# SCH_23x10_IO_EXTENDER_2023-06-17.net
KiCad netlist of a schematic drawn in EasyEDA
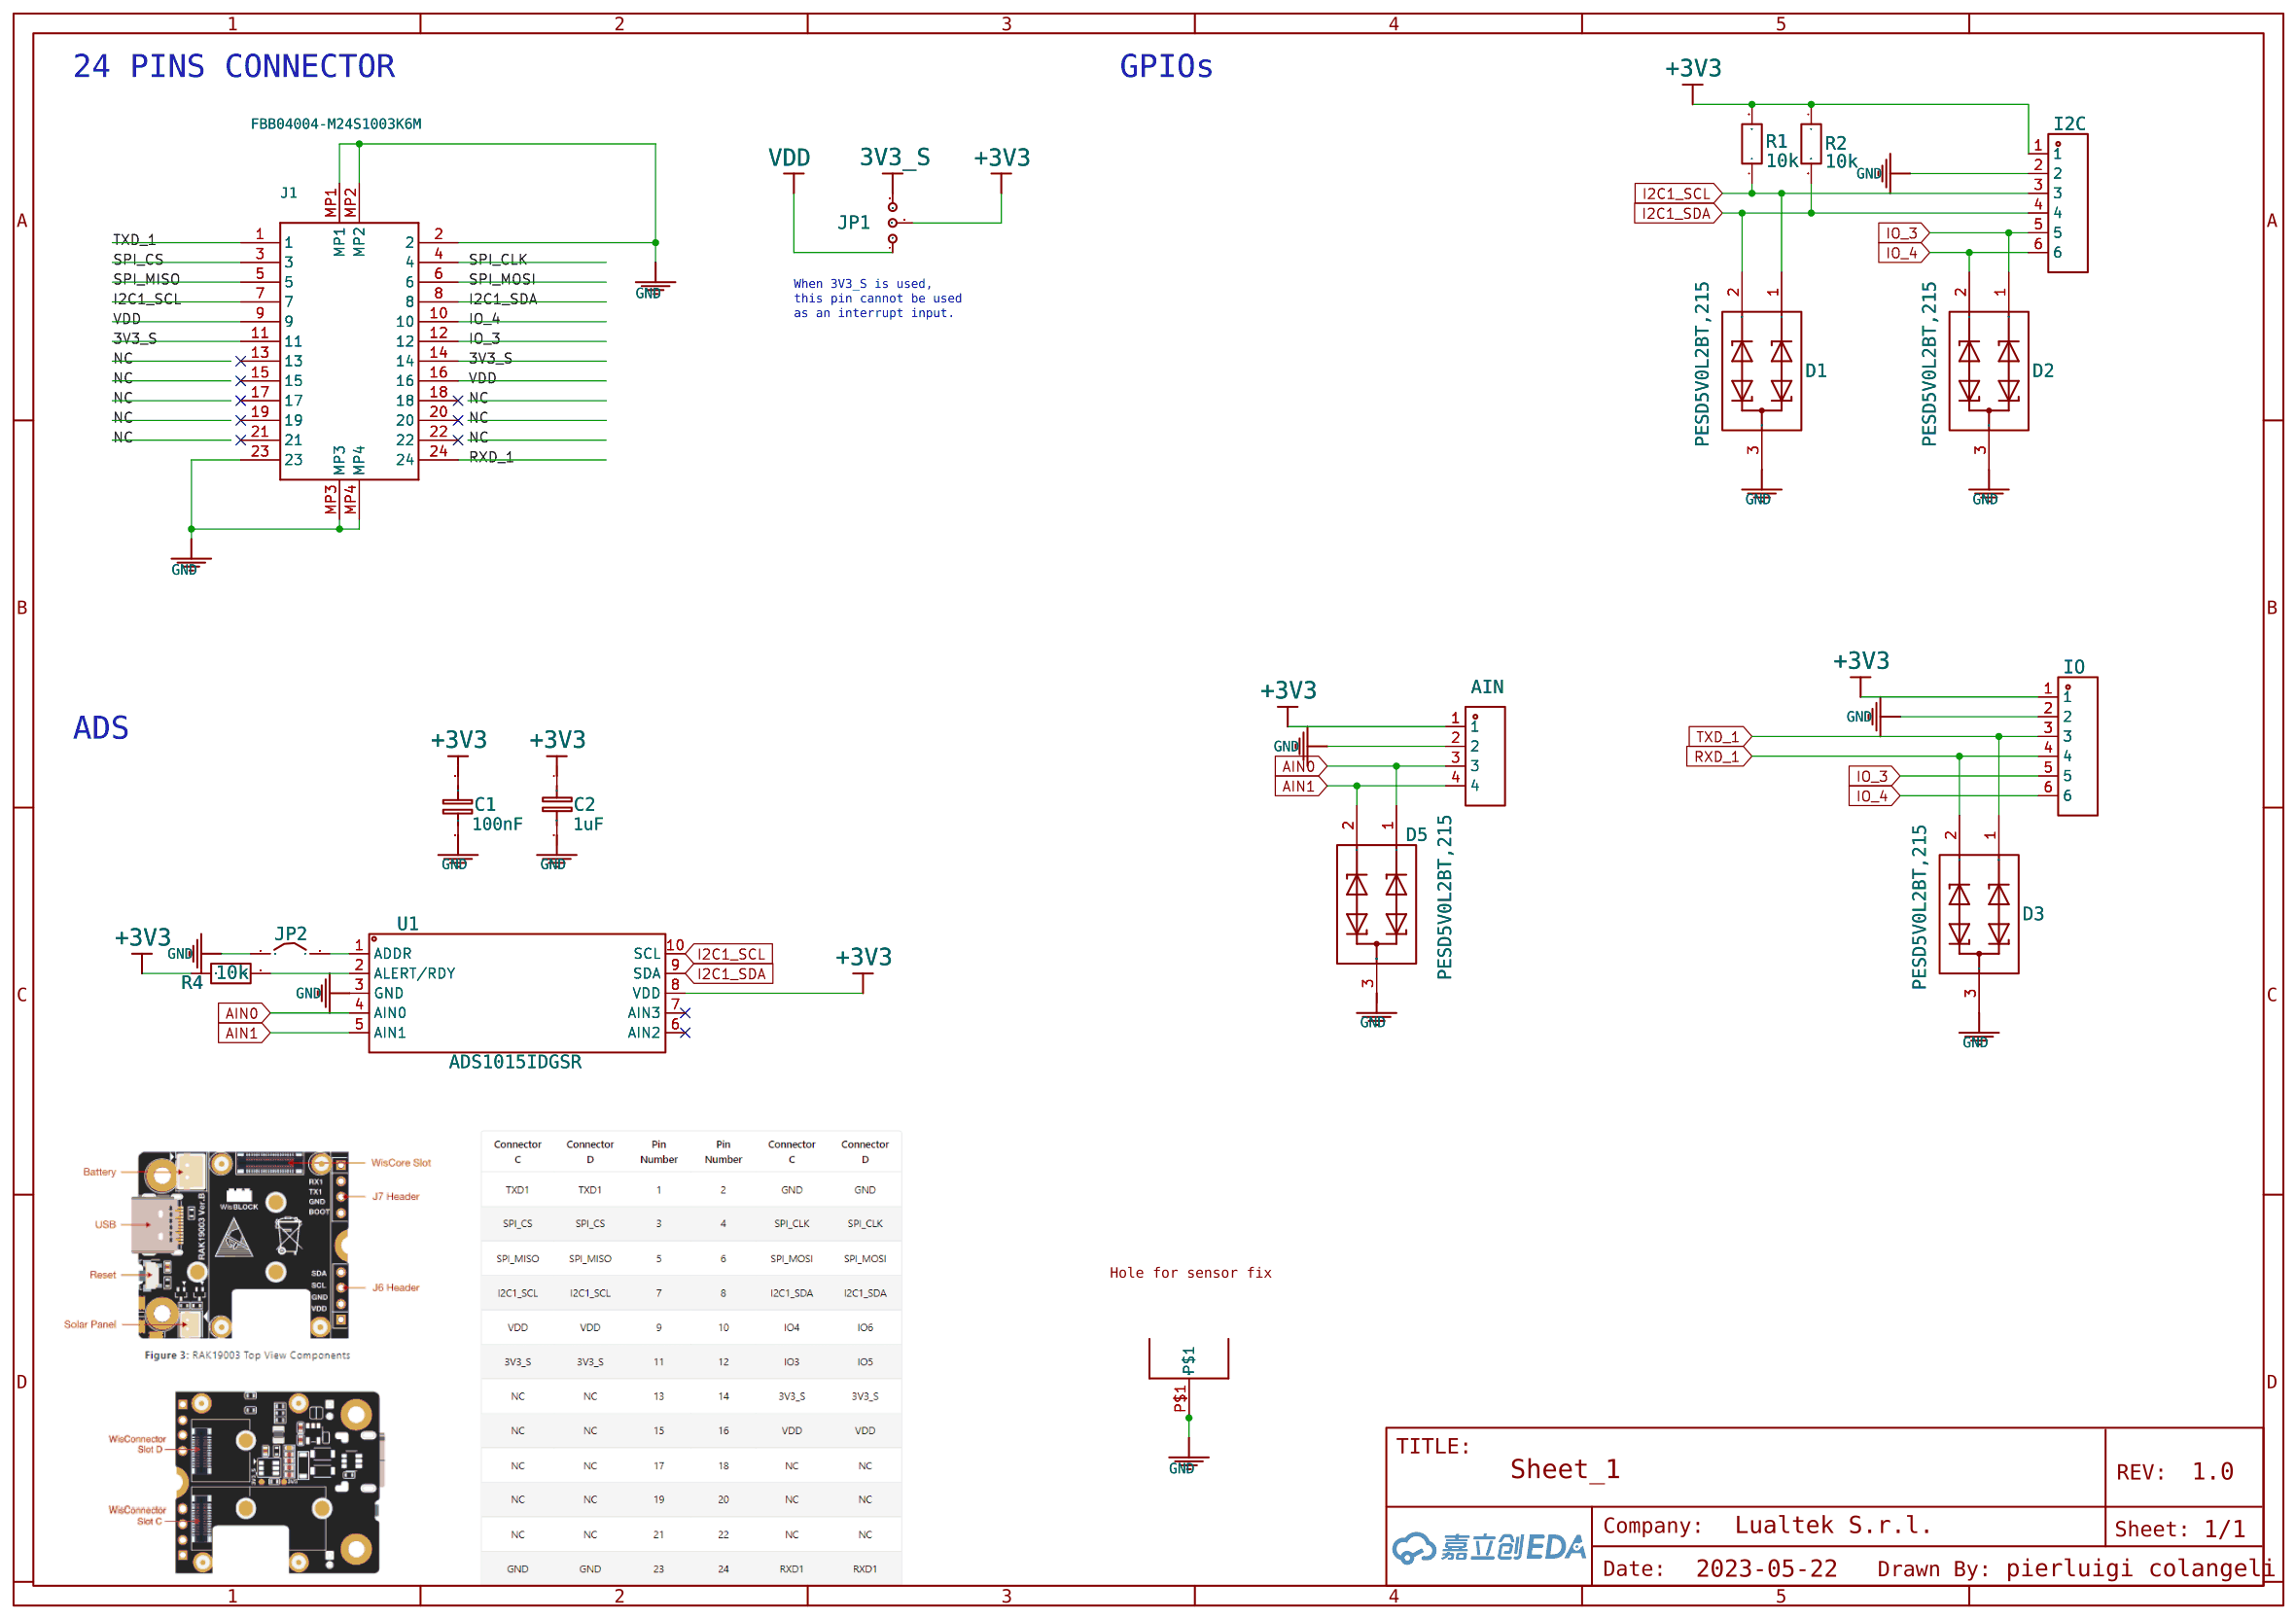
[diagram p0: schematic sheet]

(export (version "E")
  (design (tool "Eeschema 10.0.6"))
  (components
    (comp (ref "AIN")
      (value "J3")
      (fields
        (field (name "BOM_Manufacturer Part") "SM04B-SRSS-TB")
        (field (name "BOM_Supplier Part") "SM02B-SRSS-TB")
      )
      (libsource (lib "") (part "JST SH 4 pin side entry"))
    )
    (comp (ref "C1")
      (value "100nF")
      (fields
        (field (name "BOM_Manufacturer Part") "CC0603KRX7R9BB104")
        (field (name "BOM_Supplier Part") "C14663")
      )
      (libsource (lib "") (part "C_0603_EU"))
    )
    (comp (ref "C2")
      (value "1uF")
      (fields
        (field (name "BOM_Manufacturer Part") "CL10A105KB8NNNC")
        (field (name "BOM_Supplier Part") "C15849")
      )
      (libsource (lib "") (part "C_0603_EU_1"))
    )
    (comp (ref "D1")
      (value "PESD5V0L2BT,215")
      (fields (field (name "BOM_Supplier Part") "C12324"))
      (libsource (lib "") (part "PESD5V0L2BT,215"))
    )
    (comp (ref "D2")
      (value "PESD5V0L2BT,215")
      (fields (field (name "BOM_Supplier Part") "C12324"))
      (libsource (lib "") (part "PESD5V0L2BT,215"))
    )
    (comp (ref "D3")
      (value "PESD5V0L2BT,215")
      (fields (field (name "BOM_Supplier Part") "C12324"))
      (libsource (lib "") (part "PESD5V0L2BT,215"))
    )
    (comp (ref "D5")
      (value "PESD5V0L2BT,215")
      (fields (field (name "BOM_Supplier Part") "C12324"))
      (libsource (lib "") (part "PESD5V0L2BT,215"))
    )
    (comp (ref "I2C")
      (value "J1")
      (fields (field (name "BOM_Manufacturer Part") "SM06B-SRSS-TB"))
      (libsource (lib "") (part "JST SH 6 pin side entry"))
    )
    (comp (ref "IO")
      (value "J1")
      (fields (field (name "BOM_Manufacturer Part") "SM06B-SRSS-TB"))
      (libsource (lib "") (part "JST SH 6 pin side entry_1"))
    )
    (comp (ref "J1") (value "FBB04004-M24S1003K6M") (libsource (lib "") (part "Unknown_175_-720")))
    (comp (ref "JP1") (value "JUMPER_3WAY_NO_SMALL") (libsource (lib "") (part "JUMPER_3WAY_NO_SMALL")))
    (comp (ref "JP2") (value "Jumper") (libsource (lib "") (part "Jumper Solder Bridge SMD")))
    (comp (ref "R1")
      (value "10k")
      (fields
        (field (name "BOM_Manufacturer Part") "0603WAF1002T5E")
        (field (name "BOM_Supplier Part") "C25804")
      )
      (libsource (lib "") (part "R_0603_EU"))
    )
    (comp (ref "R2")
      (value "10k")
      (fields
        (field (name "BOM_Manufacturer Part") "0603WAF1002T5E")
        (field (name "BOM_Supplier Part") "C25804")
      )
      (libsource (lib "") (part "R_0603_EU_1"))
    )
    (comp (ref "R4")
      (value "10k")
      (fields
        (field (name "BOM_Manufacturer Part") "0603WAF1002T5E")
        (field (name "BOM_Supplier Part") "C25804")
      )
      (libsource (lib "") (part "R_0805_EU"))
    )
    (comp (ref "U$1") (value "RAK_SENSOR_FIX") (libsource (lib "") (part "Unknown_595_-135")))
    (comp (ref "U1")
      (value "ADS1015IDGSR")
      (fields (field (name "BOM_Supplier Part") "C193969"))
      (libsource (lib "") (part "ADS1015IDGSR"))
    )
  )
  (nets
    (net (code "1") (name "+3V3") (class "Default")
      (node (ref "AIN") (pin "1") (pinfunction "1_1") (pintype "unspecified"))
      (node (ref "C1") (pin "2") (pinfunction "2_2") (pintype "unspecified"))
      (node (ref "C2") (pin "1") (pinfunction "1_1") (pintype "unspecified"))
      (node (ref "I2C") (pin "1") (pinfunction "1_1") (pintype "unspecified"))
      (node (ref "IO") (pin "1") (pinfunction "1_1") (pintype "unspecified"))
      (node (ref "JP1") (pin "2") (pinfunction "2_2") (pintype "unspecified"))
      (node (ref "R1") (pin "2") (pinfunction "2_2") (pintype "unspecified"))
      (node (ref "R2") (pin "1") (pinfunction "1_1") (pintype "unspecified"))
      (node (ref "R4") (pin "1") (pinfunction "1_1") (pintype "unspecified"))
      (node (ref "U1") (pin "8") (pinfunction "VDD_8") (pintype "unspecified"))
    )
    (net (code "3") (name "/SPI_CLK") (class "Default")
      (node (ref "J1") (pin "4") (pinfunction "4_4") (pintype "bidirectional"))
    )
    (net (code "4") (name "/SPI_CS") (class "Default")
      (node (ref "J1") (pin "3") (pinfunction "3_3") (pintype "bidirectional"))
    )
    (net (code "5") (name "/SPI_MISO") (class "Default")
      (node (ref "J1") (pin "5") (pinfunction "5_5") (pintype "bidirectional"))
    )
    (net (code "6") (name "/SPI_MOSI") (class "Default")
      (node (ref "J1") (pin "6") (pinfunction "6_6") (pintype "bidirectional"))
    )
    (net (code "7") (name "3V3_S") (class "Default")
      (node (ref "J1") (pin "11") (pinfunction "11_11") (pintype "bidirectional"))
      (node (ref "J1") (pin "14") (pinfunction "14_14") (pintype "bidirectional"))
      (node (ref "JP1") (pin "3") (pinfunction "3_3") (pintype "unspecified"))
    )
    (net (code "8") (name "AIN0") (class "Default")
      (node (ref "AIN") (pin "3") (pinfunction "3_3") (pintype "unspecified"))
      (node (ref "D5") (pin "1") (pinfunction "C1_1") (pintype "input"))
      (node (ref "U1") (pin "4") (pinfunction "AIN0_4") (pintype "unspecified"))
    )
    (net (code "9") (name "AIN1") (class "Default")
      (node (ref "AIN") (pin "4") (pinfunction "4_4") (pintype "unspecified"))
      (node (ref "D5") (pin "2") (pinfunction "C2_2") (pintype "input"))
      (node (ref "U1") (pin "5") (pinfunction "AIN1_5") (pintype "unspecified"))
    )
    (net (code "10") (name "GND") (class "Default")
      (node (ref "AIN") (pin "2") (pinfunction "2_2") (pintype "unspecified"))
      (node (ref "C1") (pin "1") (pinfunction "1_1") (pintype "unspecified"))
      (node (ref "C2") (pin "2") (pinfunction "2_2") (pintype "unspecified"))
      (node (ref "D1") (pin "3") (pinfunction "DC_3") (pintype "input"))
      (node (ref "D2") (pin "3") (pinfunction "DC_3") (pintype "input"))
      (node (ref "D3") (pin "3") (pinfunction "DC_3") (pintype "input"))
      (node (ref "D5") (pin "3") (pinfunction "DC_3") (pintype "input"))
      (node (ref "I2C") (pin "2") (pinfunction "2_2") (pintype "unspecified"))
      (node (ref "IO") (pin "2") (pinfunction "2_2") (pintype "unspecified"))
      (node (ref "J1") (pin "2") (pinfunction "2_2") (pintype "bidirectional"))
      (node (ref "J1") (pin "23") (pinfunction "23_23") (pintype "bidirectional"))
      (node (ref "J1") (pin "MP1") (pinfunction "MP1_MP1") (pintype "bidirectional"))
      (node (ref "J1") (pin "MP2") (pinfunction "MP2_MP2") (pintype "bidirectional"))
      (node (ref "J1") (pin "MP3") (pinfunction "MP3_MP3") (pintype "bidirectional"))
      (node (ref "J1") (pin "MP4") (pinfunction "MP4_MP4") (pintype "bidirectional"))
      (node (ref "JP2") (pin "1") (pinfunction "1_1") (pintype "input"))
      (node (ref "U$1") (pin "P$1") (pinfunction "P$1_P$1") (pintype "bidirectional"))
      (node (ref "U$1") (pin "P$2") (pinfunction "P$1_P$2") (pintype "bidirectional"))
      (node (ref "U1") (pin "3") (pinfunction "GND_3") (pintype "unspecified"))
    )
    (net (code "11") (name "I2C1_SCL") (class "Default")
      (node (ref "D1") (pin "1") (pinfunction "C1_1") (pintype "input"))
      (node (ref "I2C") (pin "3") (pinfunction "3_3") (pintype "unspecified"))
      (node (ref "J1") (pin "7") (pinfunction "7_7") (pintype "bidirectional"))
      (node (ref "R1") (pin "1") (pinfunction "1_1") (pintype "unspecified"))
      (node (ref "U1") (pin "10") (pinfunction "SCL_10") (pintype "unspecified"))
    )
    (net (code "12") (name "I2C1_SDA") (class "Default")
      (node (ref "D1") (pin "2") (pinfunction "C2_2") (pintype "input"))
      (node (ref "I2C") (pin "4") (pinfunction "4_4") (pintype "unspecified"))
      (node (ref "J1") (pin "8") (pinfunction "8_8") (pintype "bidirectional"))
      (node (ref "R2") (pin "2") (pinfunction "2_2") (pintype "unspecified"))
      (node (ref "U1") (pin "9") (pinfunction "SDA_9") (pintype "unspecified"))
    )
    (net (code "13") (name "IO_3") (class "Default")
      (node (ref "D2") (pin "1") (pinfunction "C1_1") (pintype "input"))
      (node (ref "I2C") (pin "5") (pinfunction "5_5") (pintype "unspecified"))
      (node (ref "IO") (pin "5") (pinfunction "5_5") (pintype "unspecified"))
      (node (ref "J1") (pin "12") (pinfunction "12_12") (pintype "bidirectional"))
    )
    (net (code "14") (name "IO_4") (class "Default")
      (node (ref "D2") (pin "2") (pinfunction "C2_2") (pintype "input"))
      (node (ref "I2C") (pin "6") (pinfunction "6_6") (pintype "unspecified"))
      (node (ref "IO") (pin "6") (pinfunction "6_6") (pintype "unspecified"))
      (node (ref "J1") (pin "10") (pinfunction "10_10") (pintype "bidirectional"))
    )
    (net (code "15") (name "Net-(U1-ADDR)") (class "Default")
      (node (ref "JP2") (pin "2") (pinfunction "2_2") (pintype "input"))
      (node (ref "U1") (pin "1") (pinfunction "ADDR_1") (pintype "unspecified"))
    )
    (net (code "16") (name "Net-(U1-ALERT{slash}RDY)") (class "Default")
      (node (ref "R4") (pin "2") (pinfunction "2_2") (pintype "unspecified"))
      (node (ref "U1") (pin "2") (pinfunction "ALERT/RDY_2") (pintype "unspecified"))
    )
    (net (code "17") (name "RXD_1") (class "Default")
      (node (ref "D3") (pin "2") (pinfunction "C2_2") (pintype "input"))
      (node (ref "IO") (pin "4") (pinfunction "4_4") (pintype "unspecified"))
      (node (ref "J1") (pin "24") (pinfunction "24_24") (pintype "bidirectional"))
    )
    (net (code "18") (name "TXD_1") (class "Default")
      (node (ref "D3") (pin "1") (pinfunction "C1_1") (pintype "input"))
      (node (ref "IO") (pin "3") (pinfunction "3_3") (pintype "unspecified"))
      (node (ref "J1") (pin "1") (pinfunction "1_1") (pintype "bidirectional"))
    )
    (net (code "19") (name "VDD") (class "Default")
      (node (ref "J1") (pin "16") (pinfunction "16_16") (pintype "bidirectional"))
      (node (ref "J1") (pin "9") (pinfunction "9_9") (pintype "bidirectional"))
      (node (ref "JP1") (pin "1") (pinfunction "1_1") (pintype "unspecified"))
    )
    (net (code "20") (name "unconnected-(J1-Pad13)") (class "Default")
      (node (ref "J1") (pin "13") (pinfunction "13_13") (pintype "bidirectional+no_connect"))
    )
    (net (code "21") (name "unconnected-(J1-Pad15)") (class "Default")
      (node (ref "J1") (pin "15") (pinfunction "15_15") (pintype "bidirectional+no_connect"))
    )
    (net (code "22") (name "unconnected-(J1-Pad17)") (class "Default")
      (node (ref "J1") (pin "17") (pinfunction "17_17") (pintype "bidirectional+no_connect"))
    )
    (net (code "23") (name "unconnected-(J1-Pad18)") (class "Default")
      (node (ref "J1") (pin "18") (pinfunction "18_18") (pintype "bidirectional+no_connect"))
    )
    (net (code "24") (name "unconnected-(J1-Pad19)") (class "Default")
      (node (ref "J1") (pin "19") (pinfunction "19_19") (pintype "bidirectional+no_connect"))
    )
    (net (code "25") (name "unconnected-(J1-Pad20)") (class "Default")
      (node (ref "J1") (pin "20") (pinfunction "20_20") (pintype "bidirectional+no_connect"))
    )
    (net (code "26") (name "unconnected-(J1-Pad21)") (class "Default")
      (node (ref "J1") (pin "21") (pinfunction "21_21") (pintype "bidirectional+no_connect"))
    )
    (net (code "27") (name "unconnected-(J1-Pad22)") (class "Default")
      (node (ref "J1") (pin "22") (pinfunction "22_22") (pintype "bidirectional+no_connect"))
    )
    (net (code "28") (name "unconnected-(U1-AIN2-Pad6)") (class "Default")
      (node (ref "U1") (pin "6") (pinfunction "AIN2_6") (pintype "unspecified+no_connect"))
    )
    (net (code "29") (name "unconnected-(U1-AIN3-Pad7)") (class "Default")
      (node (ref "U1") (pin "7") (pinfunction "AIN3_7") (pintype "unspecified+no_connect"))
    )
  )
)
